# FPGA_System_Monitor.net
KiCad netlist of a schematic drawn in Altium Designer
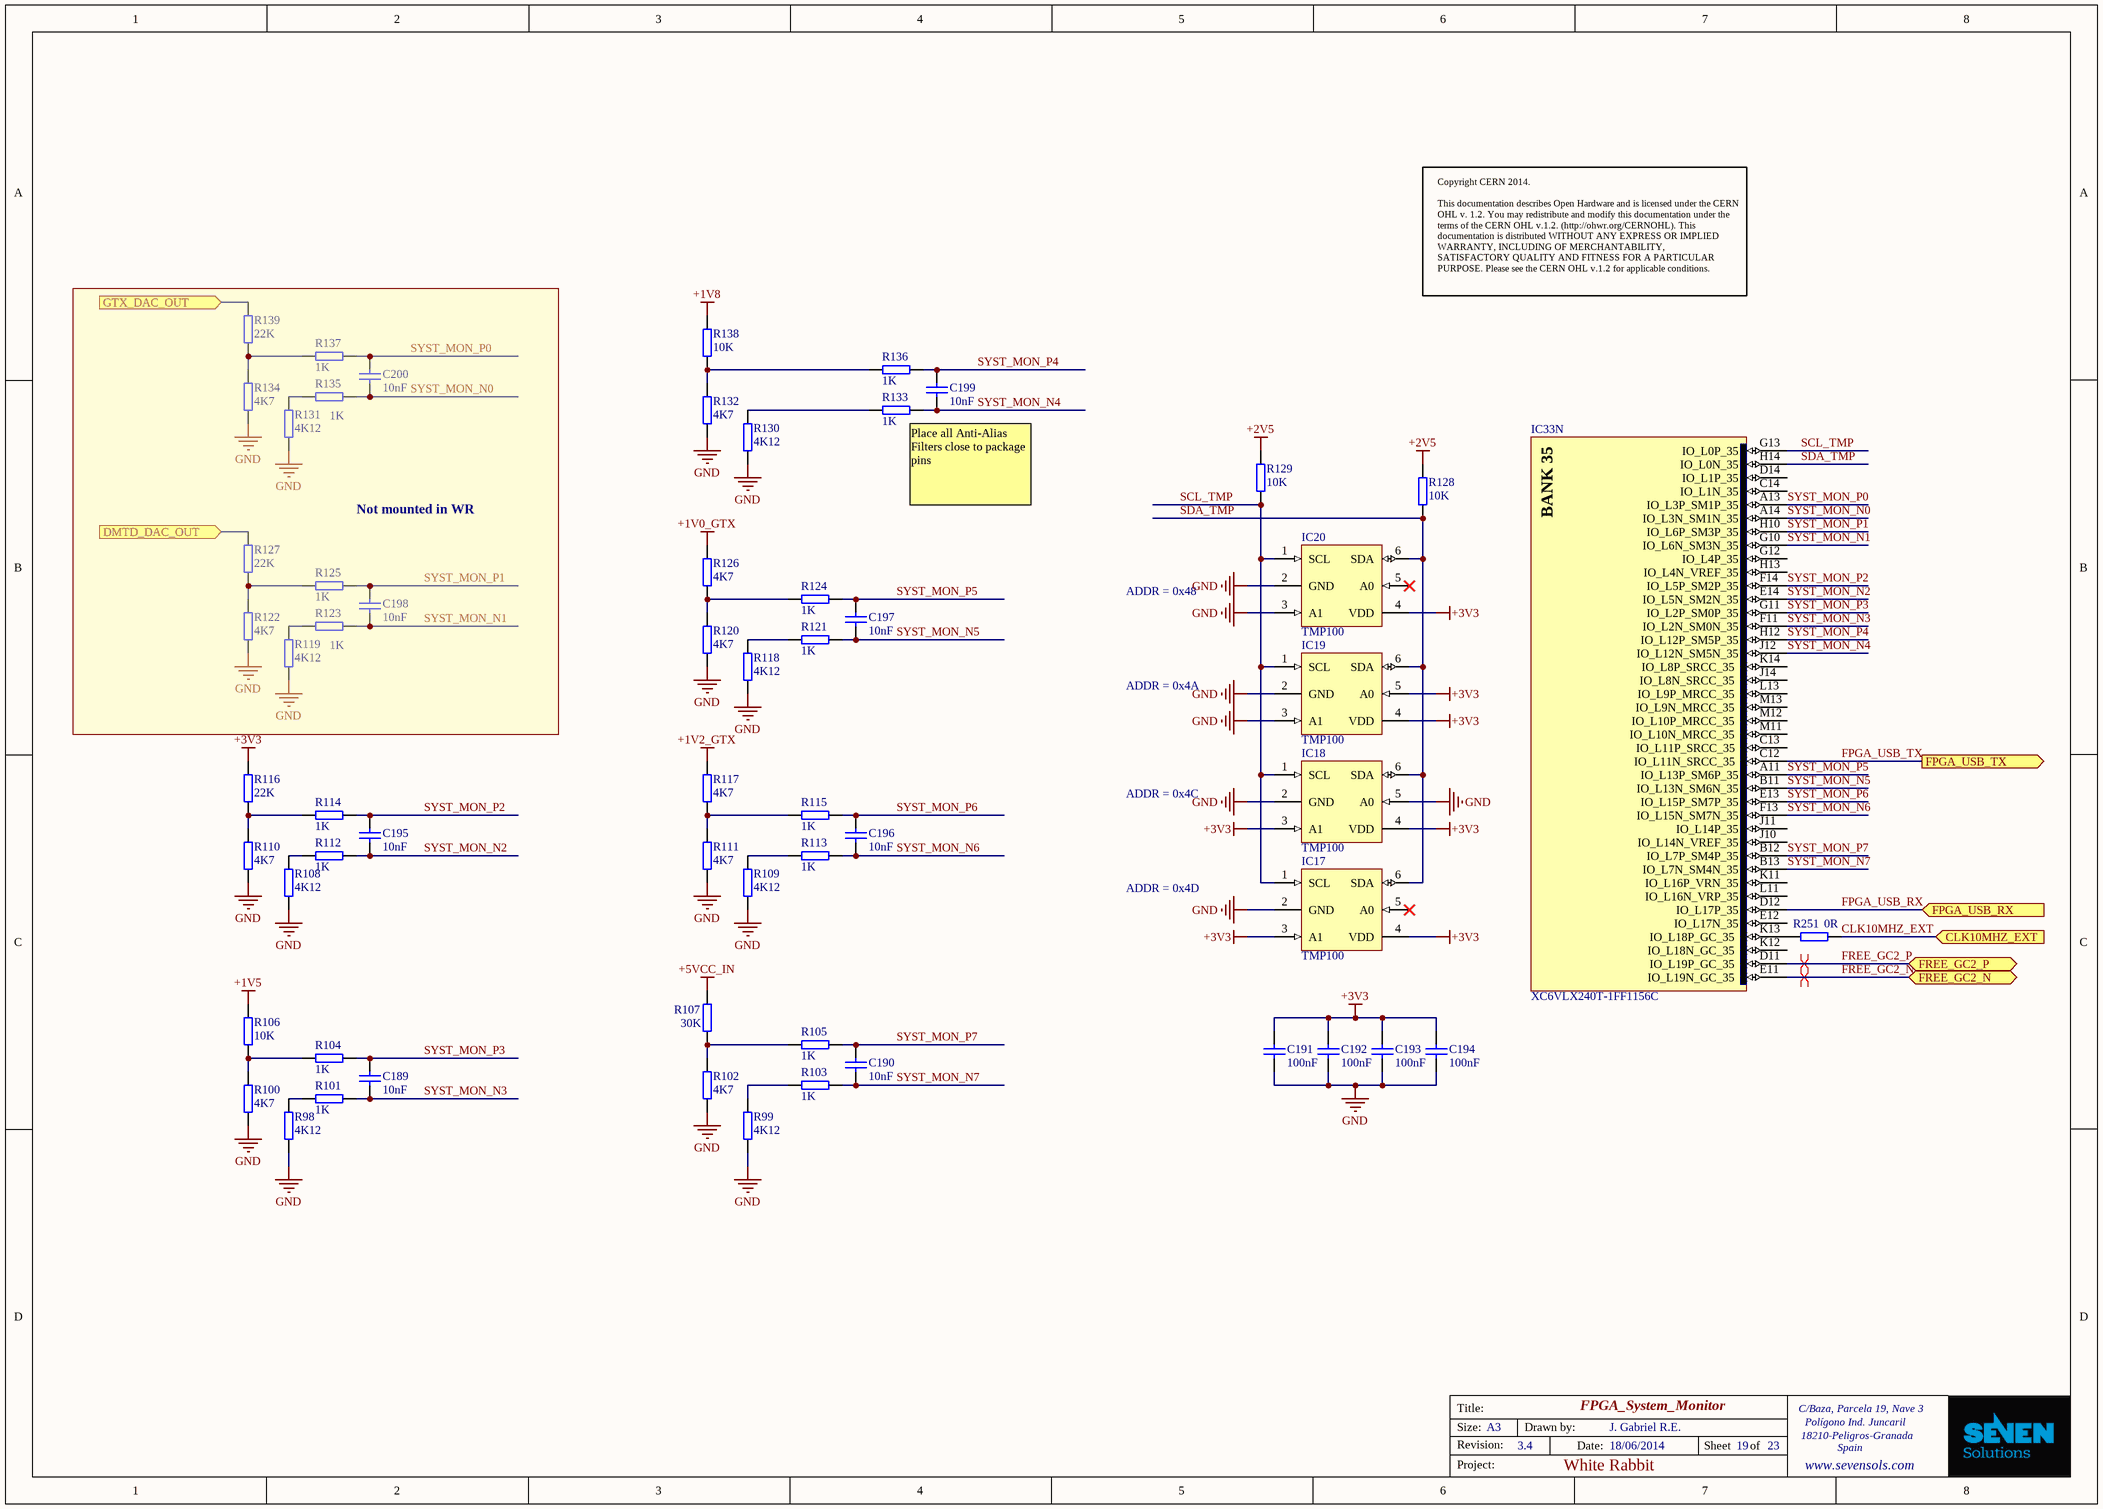
[diagram p0: FPGA_System_Monitor.SchDoc]

(export (version "E")
  (design (tool "Eeschema 10.0.6"))
  (components
    (comp (ref "C189")
      (value "10nF")
      (footprint "CC1005-0402")
      (description "Capacitor")
      (fields
        (field (name "TOLERANCE") "±10%")
        (field (name "VOLTAGE") "25V")
        (field (name "PUBLISHER") "Altium Limited")
      )
      (libsource (lib "wr_switch") (part "Cap"))
    )
    (comp (ref "C190")
      (value "10nF")
      (footprint "CC1005-0402")
      (description "Capacitor")
      (fields
        (field (name "TOLERANCE") "±10%")
        (field (name "VOLTAGE") "25V")
        (field (name "PUBLISHER") "Altium Limited")
      )
      (libsource (lib "wr_switch") (part "Cap"))
    )
    (comp (ref "C191")
      (value "100nF")
      (footprint "CC1005-0402")
      (description "Capacitor")
      (fields
        (field (name "TOLERANCE") "±10%")
        (field (name "VOLTAGE") "16V")
        (field (name "PUBLISHER") "Altium Limited")
      )
      (libsource (lib "wr_switch") (part "Cap"))
    )
    (comp (ref "C192")
      (value "100nF")
      (footprint "CC1005-0402")
      (description "Capacitor")
      (fields
        (field (name "TOLERANCE") "±10%")
        (field (name "VOLTAGE") "16V")
        (field (name "PUBLISHER") "Altium Limited")
      )
      (libsource (lib "wr_switch") (part "Cap"))
    )
    (comp (ref "C193")
      (value "100nF")
      (footprint "CC1005-0402")
      (description "Capacitor")
      (fields
        (field (name "TOLERANCE") "±10%")
        (field (name "VOLTAGE") "16V")
        (field (name "PUBLISHER") "Altium Limited")
      )
      (libsource (lib "wr_switch") (part "Cap"))
    )
    (comp (ref "C194")
      (value "100nF")
      (footprint "CC1005-0402")
      (description "Capacitor")
      (fields
        (field (name "TOLERANCE") "±10%")
        (field (name "VOLTAGE") "16V")
        (field (name "PUBLISHER") "Altium Limited")
      )
      (libsource (lib "wr_switch") (part "Cap"))
    )
    (comp (ref "C195")
      (value "10nF")
      (footprint "CC1005-0402")
      (description "Capacitor")
      (fields
        (field (name "TOLERANCE") "±10%")
        (field (name "VOLTAGE") "25V")
        (field (name "PUBLISHER") "Altium Limited")
      )
      (libsource (lib "wr_switch") (part "Cap"))
    )
    (comp (ref "C196")
      (value "10nF")
      (footprint "CC1005-0402")
      (description "Capacitor")
      (fields
        (field (name "TOLERANCE") "±10%")
        (field (name "VOLTAGE") "25V")
        (field (name "PUBLISHER") "Altium Limited")
      )
      (libsource (lib "wr_switch") (part "Cap"))
    )
    (comp (ref "C197")
      (value "10nF")
      (footprint "CC1005-0402")
      (description "Capacitor")
      (fields
        (field (name "TOLERANCE") "±10%")
        (field (name "VOLTAGE") "25V")
        (field (name "PUBLISHER") "Altium Limited")
      )
      (libsource (lib "wr_switch") (part "Cap"))
    )
    (comp (ref "C198")
      (value "10nF")
      (footprint "CC1005-0402")
      (description "Capacitor")
      (fields
        (field (name "TOLERANCE") "±10%")
        (field (name "VOLTAGE") "25V")
        (field (name "PUBLISHER") "Altium Limited")
      )
      (libsource (lib "wr_switch") (part "Cap"))
    )
    (comp (ref "C199")
      (value "10nF")
      (footprint "CC1005-0402")
      (description "Capacitor")
      (fields
        (field (name "TOLERANCE") "±10%")
        (field (name "VOLTAGE") "25V")
        (field (name "PUBLISHER") "Altium Limited")
      )
      (libsource (lib "wr_switch") (part "Cap"))
    )
    (comp (ref "C200")
      (value "10nF")
      (footprint "CC1005-0402")
      (description "Capacitor")
      (fields
        (field (name "TOLERANCE") "±10%")
        (field (name "VOLTAGE") "25V")
        (field (name "PUBLISHER") "Altium Limited")
      )
      (libsource (lib "wr_switch") (part "Cap"))
    )
    (comp (ref "IC17")
      (value "TMP100")
      (footprint "SOT23A-6L")
      (description "I2C temp. sensor")
      (libsource (lib "wr_switch") (part "TMP100"))
    )
    (comp (ref "IC18")
      (value "TMP100")
      (footprint "SOT23A-6L")
      (description "I2C temp. sensor")
      (libsource (lib "wr_switch") (part "TMP100"))
    )
    (comp (ref "IC19")
      (value "TMP100")
      (footprint "SOT23A-6L")
      (description "I2C temp. sensor")
      (libsource (lib "wr_switch") (part "TMP100"))
    )
    (comp (ref "IC20")
      (value "TMP100")
      (footprint "SOT23A-6L")
      (description "I2C temp. sensor")
      (libsource (lib "wr_switch") (part "TMP100"))
    )
    (comp (ref "IC33")
      (value "XC6VLX240T-1FF1156C")
      (footprint "FF1156")
      (fields (field (name "PUBLISHER") "Altium Limited"))
      (libsource (lib "Xilinx Virtex-6") (part "XC6VLX240T-1FF1156C"))
    )
    (comp (ref "R98")
      (value "4K12")
      (footprint "0402")
      (description "SMD Resistor")
      (fields (field (name "TOLERANCE") "±1%"))
      (libsource (lib "wr_switch") (part "RES_SMD"))
    )
    (comp (ref "R99")
      (value "4K12")
      (footprint "0402")
      (description "SMD Resistor")
      (fields (field (name "TOLERANCE") "±1%"))
      (libsource (lib "wr_switch") (part "RES_SMD"))
    )
    (comp (ref "R100")
      (value "4K7")
      (footprint "0402")
      (description "SMD Resistor")
      (fields (field (name "TOLERANCE") "±1%"))
      (libsource (lib "wr_switch") (part "RES_SMD"))
    )
    (comp (ref "R101")
      (value "1K")
      (footprint "0402")
      (description "SMD Resistor")
      (fields (field (name "TOLERANCE") "±1%"))
      (libsource (lib "wr_switch") (part "RES_SMD"))
    )
    (comp (ref "R102")
      (value "4K7")
      (footprint "0402")
      (description "SMD Resistor")
      (fields (field (name "TOLERANCE") "±1%"))
      (libsource (lib "wr_switch") (part "RES_SMD"))
    )
    (comp (ref "R103")
      (value "1K")
      (footprint "0402")
      (description "SMD Resistor")
      (fields (field (name "TOLERANCE") "±1%"))
      (libsource (lib "wr_switch") (part "RES_SMD"))
    )
    (comp (ref "R104")
      (value "1K")
      (footprint "0402")
      (description "SMD Resistor")
      (fields (field (name "TOLERANCE") "±1%"))
      (libsource (lib "wr_switch") (part "RES_SMD"))
    )
    (comp (ref "R105")
      (value "1K")
      (footprint "0402")
      (description "SMD Resistor")
      (fields (field (name "TOLERANCE") "±1%"))
      (libsource (lib "wr_switch") (part "RES_SMD"))
    )
    (comp (ref "R106")
      (value "10K")
      (footprint "0402")
      (description "SMD Resistor")
      (fields (field (name "TOLERANCE") "±1%") (field (name "Comment") "10k"))
      (libsource (lib "wr_switch") (part "RES_SMD"))
    )
    (comp (ref "R107")
      (value "30K")
      (footprint "0402")
      (description "SMD Resistor")
      (fields (field (name "TOLERANCE") "±1%"))
      (libsource (lib "wr_switch") (part "RES_SMD"))
    )
    (comp (ref "R108")
      (value "4K12")
      (footprint "0402")
      (description "SMD Resistor")
      (fields (field (name "TOLERANCE") "±1%"))
      (libsource (lib "wr_switch") (part "RES_SMD"))
    )
    (comp (ref "R109")
      (value "4K12")
      (footprint "0402")
      (description "SMD Resistor")
      (fields (field (name "TOLERANCE") "±1%"))
      (libsource (lib "wr_switch") (part "RES_SMD"))
    )
    (comp (ref "R110")
      (value "4K7")
      (footprint "0402")
      (description "SMD Resistor")
      (fields (field (name "TOLERANCE") "±1%"))
      (libsource (lib "wr_switch") (part "RES_SMD"))
    )
    (comp (ref "R111")
      (value "4K7")
      (footprint "0402")
      (description "SMD Resistor")
      (fields (field (name "TOLERANCE") "±1%"))
      (libsource (lib "wr_switch") (part "RES_SMD"))
    )
    (comp (ref "R112")
      (value "1K")
      (footprint "0402")
      (description "SMD Resistor")
      (fields (field (name "TOLERANCE") "±1%"))
      (libsource (lib "wr_switch") (part "RES_SMD"))
    )
    (comp (ref "R113")
      (value "1K")
      (footprint "0402")
      (description "SMD Resistor")
      (fields (field (name "TOLERANCE") "±1%"))
      (libsource (lib "wr_switch") (part "RES_SMD"))
    )
    (comp (ref "R114")
      (value "1K")
      (footprint "0402")
      (description "SMD Resistor")
      (fields (field (name "TOLERANCE") "±1%"))
      (libsource (lib "wr_switch") (part "RES_SMD"))
    )
    (comp (ref "R115")
      (value "1K")
      (footprint "0402")
      (description "SMD Resistor")
      (fields (field (name "TOLERANCE") "±1%"))
      (libsource (lib "wr_switch") (part "RES_SMD"))
    )
    (comp (ref "R116")
      (value "22K")
      (footprint "0402")
      (description "SMD Resistor")
      (fields (field (name "TOLERANCE") "±1%"))
      (libsource (lib "wr_switch") (part "RES_SMD"))
    )
    (comp (ref "R117")
      (value "4K7")
      (footprint "0402")
      (description "SMD Resistor")
      (fields (field (name "TOLERANCE") "±1%"))
      (libsource (lib "wr_switch") (part "RES_SMD"))
    )
    (comp (ref "R118")
      (value "4K12")
      (footprint "0402")
      (description "SMD Resistor")
      (fields (field (name "TOLERANCE") "±1%"))
      (libsource (lib "wr_switch") (part "RES_SMD"))
    )
    (comp (ref "R119")
      (value "4K12")
      (footprint "0402")
      (description "SMD Resistor")
      (fields (field (name "TOLERANCE") "±1%"))
      (libsource (lib "wr_switch") (part "RES_SMD"))
    )
    (comp (ref "R120")
      (value "4K7")
      (footprint "0402")
      (description "SMD Resistor")
      (fields (field (name "TOLERANCE") "±1%"))
      (libsource (lib "wr_switch") (part "RES_SMD"))
    )
    (comp (ref "R121")
      (value "1K")
      (footprint "0402")
      (description "SMD Resistor")
      (fields (field (name "TOLERANCE") "±1%"))
      (libsource (lib "wr_switch") (part "RES_SMD"))
    )
    (comp (ref "R122")
      (value "4K7")
      (footprint "0402")
      (description "SMD Resistor")
      (fields (field (name "TOLERANCE") "±1%"))
      (libsource (lib "wr_switch") (part "RES_SMD"))
    )
    (comp (ref "R123")
      (value "1K")
      (footprint "0402")
      (description "SMD Resistor")
      (fields (field (name "TOLERANCE") "±1%"))
      (libsource (lib "wr_switch") (part "RES_SMD"))
    )
    (comp (ref "R124")
      (value "1K")
      (footprint "0402")
      (description "SMD Resistor")
      (fields (field (name "TOLERANCE") "±1%"))
      (libsource (lib "wr_switch") (part "RES_SMD"))
    )
    (comp (ref "R125")
      (value "1K")
      (footprint "0402")
      (description "SMD Resistor")
      (fields (field (name "TOLERANCE") "±1%"))
      (libsource (lib "wr_switch") (part "RES_SMD"))
    )
    (comp (ref "R126")
      (value "4K7")
      (footprint "0402")
      (description "SMD Resistor")
      (fields (field (name "TOLERANCE") "±1%"))
      (libsource (lib "wr_switch") (part "RES_SMD"))
    )
    (comp (ref "R127")
      (value "22K")
      (footprint "0402")
      (description "SMD Resistor")
      (fields (field (name "TOLERANCE") "±1%"))
      (libsource (lib "wr_switch") (part "RES_SMD"))
    )
    (comp (ref "R128")
      (value "10K")
      (footprint "0402")
      (description "SMD Resistor")
      (fields (field (name "TOLERANCE") "±1%") (field (name "Comment") "10k"))
      (libsource (lib "wr_switch") (part "RES_SMD"))
    )
    (comp (ref "R129")
      (value "10K")
      (footprint "0402")
      (description "SMD Resistor")
      (fields (field (name "TOLERANCE") "±1%") (field (name "Comment") "10k"))
      (libsource (lib "wr_switch") (part "RES_SMD"))
    )
    (comp (ref "R130")
      (value "4K12")
      (footprint "0402")
      (description "SMD Resistor")
      (fields (field (name "TOLERANCE") "±1%"))
      (libsource (lib "wr_switch") (part "RES_SMD"))
    )
    (comp (ref "R131")
      (value "4K12")
      (footprint "0402")
      (description "SMD Resistor")
      (fields (field (name "TOLERANCE") "±1%"))
      (libsource (lib "wr_switch") (part "RES_SMD"))
    )
    (comp (ref "R132")
      (value "4K7")
      (footprint "0402")
      (description "SMD Resistor")
      (fields (field (name "TOLERANCE") "±1%"))
      (libsource (lib "wr_switch") (part "RES_SMD"))
    )
    (comp (ref "R133")
      (value "1K")
      (footprint "0402")
      (description "SMD Resistor")
      (fields (field (name "TOLERANCE") "±1%"))
      (libsource (lib "wr_switch") (part "RES_SMD"))
    )
    (comp (ref "R134")
      (value "4K7")
      (footprint "0402")
      (description "SMD Resistor")
      (fields (field (name "TOLERANCE") "±1%"))
      (libsource (lib "wr_switch") (part "RES_SMD"))
    )
    (comp (ref "R135")
      (value "1K")
      (footprint "0402")
      (description "SMD Resistor")
      (fields (field (name "TOLERANCE") "±1%"))
      (libsource (lib "wr_switch") (part "RES_SMD"))
    )
    (comp (ref "R136")
      (value "1K")
      (footprint "0402")
      (description "SMD Resistor")
      (fields (field (name "TOLERANCE") "±1%"))
      (libsource (lib "wr_switch") (part "RES_SMD"))
    )
    (comp (ref "R137")
      (value "1K")
      (footprint "0402")
      (description "SMD Resistor")
      (fields (field (name "TOLERANCE") "±1%"))
      (libsource (lib "wr_switch") (part "RES_SMD"))
    )
    (comp (ref "R138")
      (value "10K")
      (footprint "0402")
      (description "SMD Resistor")
      (fields (field (name "TOLERANCE") "±1%") (field (name "Comment") "10k"))
      (libsource (lib "wr_switch") (part "RES_SMD"))
    )
    (comp (ref "R139")
      (value "22K")
      (footprint "0402")
      (description "SMD Resistor")
      (fields (field (name "TOLERANCE") "±1%"))
      (libsource (lib "wr_switch") (part "RES_SMD"))
    )
    (comp (ref "R251")
      (value "0R")
      (footprint "0402")
      (description "SMD Resistor")
      (fields (field (name "TOLERANCE") "Jumper"))
      (libsource (lib "wr_switch") (part "RES_SMD"))
    )
  )
  (nets
    (net (code "1") (name "+1V0_GTX") (class "Default")
      (node (ref "R126") (pin "2") (pinfunction "2_2") (pintype "passive"))
    )
    (net (code "2") (name "+1V2_GTX") (class "Default")
      (node (ref "R117") (pin "2") (pinfunction "2_2") (pintype "passive"))
    )
    (net (code "3") (name "+1V5") (class "Default")
      (node (ref "R106") (pin "2") (pinfunction "2_2") (pintype "passive"))
    )
    (net (code "4") (name "+1V8") (class "Default")
      (node (ref "R138") (pin "2") (pinfunction "2_2") (pintype "passive"))
    )
    (net (code "5") (name "+2V5") (class "Default")
      (node (ref "R128") (pin "2") (pinfunction "2_2") (pintype "passive"))
      (node (ref "R129") (pin "2") (pinfunction "2_2") (pintype "passive"))
    )
    (net (code "6") (name "+3V3") (class "Default")
      (node (ref "C191") (pin "1") (pinfunction "1_1") (pintype "passive"))
      (node (ref "C192") (pin "1") (pinfunction "1_1") (pintype "passive"))
      (node (ref "C193") (pin "1") (pinfunction "1_1") (pintype "passive"))
      (node (ref "C194") (pin "1") (pinfunction "1_1") (pintype "passive"))
      (node (ref "IC17") (pin "3") (pinfunction "A1_3") (pintype "input"))
      (node (ref "IC17") (pin "4") (pinfunction "VDD_4") (pintype "power_in"))
      (node (ref "IC18") (pin "3") (pinfunction "A1_3") (pintype "input"))
      (node (ref "IC18") (pin "4") (pinfunction "VDD_4") (pintype "power_in"))
      (node (ref "IC19") (pin "4") (pinfunction "VDD_4") (pintype "power_in"))
      (node (ref "IC19") (pin "5") (pinfunction "A0_5") (pintype "input"))
      (node (ref "IC20") (pin "4") (pinfunction "VDD_4") (pintype "power_in"))
      (node (ref "R116") (pin "2") (pinfunction "2_2") (pintype "passive"))
    )
    (net (code "7") (name "+5VCC_IN") (class "Default")
      (node (ref "R107") (pin "2") (pinfunction "2_2") (pintype "passive"))
    )
    (net (code "8") (name "/CLK10MHZ_EXT") (class "Default")
      (node (ref "R251") (pin "1") (pinfunction "1_1") (pintype "passive"))
    )
    (net (code "9") (name "/DMTD_DAC_OUT") (class "Default")
      (node (ref "R127") (pin "2") (pinfunction "2_2") (pintype "passive"))
    )
    (net (code "10") (name "/FPGA_USB_RX") (class "Default")
      (node (ref "IC33") (pin "D12") (pinfunction "IO_L17P_35_D12") (pintype "bidirectional"))
    )
    (net (code "11") (name "/FPGA_USB_TX") (class "Default")
      (node (ref "IC33") (pin "C12") (pinfunction "IO_L11N_SRCC_35_C12") (pintype "bidirectional"))
    )
    (net (code "12") (name "/FREE_GC2_N") (class "Default")
      (node (ref "IC33") (pin "E11") (pinfunction "IO_L19N_GC_35_E11") (pintype "bidirectional"))
    )
    (net (code "13") (name "/FREE_GC2_P") (class "Default")
      (node (ref "IC33") (pin "D11") (pinfunction "IO_L19P_GC_35_D11") (pintype "bidirectional"))
    )
    (net (code "14") (name "/GTX_DAC_OUT") (class "Default")
      (node (ref "R139") (pin "2") (pinfunction "2_2") (pintype "passive"))
    )
    (net (code "15") (name "/SCL_TMP") (class "Default")
      (node (ref "IC17") (pin "1") (pinfunction "SCL_1") (pintype "input"))
      (node (ref "IC18") (pin "1") (pinfunction "SCL_1") (pintype "input"))
      (node (ref "IC19") (pin "1") (pinfunction "SCL_1") (pintype "input"))
      (node (ref "IC20") (pin "1") (pinfunction "SCL_1") (pintype "input"))
      (node (ref "IC33") (pin "G13") (pinfunction "IO_L0P_35_G13") (pintype "bidirectional"))
      (node (ref "R129") (pin "1") (pinfunction "1_1") (pintype "passive"))
    )
    (net (code "16") (name "/SDA_TMP") (class "Default")
      (node (ref "IC17") (pin "6") (pinfunction "SDA_6") (pintype "bidirectional"))
      (node (ref "IC18") (pin "6") (pinfunction "SDA_6") (pintype "bidirectional"))
      (node (ref "IC19") (pin "6") (pinfunction "SDA_6") (pintype "bidirectional"))
      (node (ref "IC20") (pin "6") (pinfunction "SDA_6") (pintype "bidirectional"))
      (node (ref "IC33") (pin "H14") (pinfunction "IO_L0N_35_H14") (pintype "bidirectional"))
      (node (ref "R128") (pin "1") (pinfunction "1_1") (pintype "passive"))
    )
    (net (code "17") (name "/SYST_MON_N0") (class "Default")
      (node (ref "C200") (pin "1") (pinfunction "1_1") (pintype "passive"))
      (node (ref "IC33") (pin "A14") (pinfunction "IO_L3N_SM1N_35_A14") (pintype "bidirectional"))
      (node (ref "R135") (pin "1") (pinfunction "1_1") (pintype "passive"))
    )
    (net (code "18") (name "/SYST_MON_N1") (class "Default")
      (node (ref "C198") (pin "1") (pinfunction "1_1") (pintype "passive"))
      (node (ref "IC33") (pin "G10") (pinfunction "IO_L6N_SM3N_35_G10") (pintype "bidirectional"))
      (node (ref "R123") (pin "1") (pinfunction "1_1") (pintype "passive"))
    )
    (net (code "19") (name "/SYST_MON_N2") (class "Default")
      (node (ref "C195") (pin "1") (pinfunction "1_1") (pintype "passive"))
      (node (ref "IC33") (pin "E14") (pinfunction "IO_L5N_SM2N_35_E14") (pintype "bidirectional"))
      (node (ref "R112") (pin "1") (pinfunction "1_1") (pintype "passive"))
    )
    (net (code "20") (name "/SYST_MON_N3") (class "Default")
      (node (ref "C189") (pin "1") (pinfunction "1_1") (pintype "passive"))
      (node (ref "IC33") (pin "F11") (pinfunction "IO_L2N_SM0N_35_F11") (pintype "bidirectional"))
      (node (ref "R101") (pin "1") (pinfunction "1_1") (pintype "passive"))
    )
    (net (code "21") (name "/SYST_MON_N4") (class "Default")
      (node (ref "C199") (pin "1") (pinfunction "1_1") (pintype "passive"))
      (node (ref "IC33") (pin "J12") (pinfunction "IO_L12N_SM5N_35_J12") (pintype "bidirectional"))
      (node (ref "R133") (pin "1") (pinfunction "1_1") (pintype "passive"))
    )
    (net (code "22") (name "/SYST_MON_N5") (class "Default")
      (node (ref "C197") (pin "1") (pinfunction "1_1") (pintype "passive"))
      (node (ref "IC33") (pin "B11") (pinfunction "IO_L13N_SM6N_35_B11") (pintype "bidirectional"))
      (node (ref "R121") (pin "1") (pinfunction "1_1") (pintype "passive"))
    )
    (net (code "23") (name "/SYST_MON_N6") (class "Default")
      (node (ref "C196") (pin "1") (pinfunction "1_1") (pintype "passive"))
      (node (ref "IC33") (pin "F13") (pinfunction "IO_L15N_SM7N_35_F13") (pintype "bidirectional"))
      (node (ref "R113") (pin "1") (pinfunction "1_1") (pintype "passive"))
    )
    (net (code "24") (name "/SYST_MON_N7") (class "Default")
      (node (ref "C190") (pin "1") (pinfunction "1_1") (pintype "passive"))
      (node (ref "IC33") (pin "B13") (pinfunction "IO_L7N_SM4N_35_B13") (pintype "bidirectional"))
      (node (ref "R103") (pin "1") (pinfunction "1_1") (pintype "passive"))
    )
    (net (code "25") (name "/SYST_MON_P0") (class "Default")
      (node (ref "C200") (pin "2") (pinfunction "2_2") (pintype "passive"))
      (node (ref "IC33") (pin "A13") (pinfunction "IO_L3P_SM1P_35_A13") (pintype "bidirectional"))
      (node (ref "R137") (pin "1") (pinfunction "1_1") (pintype "passive"))
    )
    (net (code "26") (name "/SYST_MON_P1") (class "Default")
      (node (ref "C198") (pin "2") (pinfunction "2_2") (pintype "passive"))
      (node (ref "IC33") (pin "H10") (pinfunction "IO_L6P_SM3P_35_H10") (pintype "bidirectional"))
      (node (ref "R125") (pin "1") (pinfunction "1_1") (pintype "passive"))
    )
    (net (code "27") (name "/SYST_MON_P2") (class "Default")
      (node (ref "C195") (pin "2") (pinfunction "2_2") (pintype "passive"))
      (node (ref "IC33") (pin "F14") (pinfunction "IO_L5P_SM2P_35_F14") (pintype "bidirectional"))
      (node (ref "R114") (pin "1") (pinfunction "1_1") (pintype "passive"))
    )
    (net (code "28") (name "/SYST_MON_P3") (class "Default")
      (node (ref "C189") (pin "2") (pinfunction "2_2") (pintype "passive"))
      (node (ref "IC33") (pin "G11") (pinfunction "IO_L2P_SM0P_35_G11") (pintype "bidirectional"))
      (node (ref "R104") (pin "1") (pinfunction "1_1") (pintype "passive"))
    )
    (net (code "29") (name "/SYST_MON_P4") (class "Default")
      (node (ref "C199") (pin "2") (pinfunction "2_2") (pintype "passive"))
      (node (ref "IC33") (pin "H12") (pinfunction "IO_L12P_SM5P_35_H12") (pintype "bidirectional"))
      (node (ref "R136") (pin "1") (pinfunction "1_1") (pintype "passive"))
    )
    (net (code "30") (name "/SYST_MON_P5") (class "Default")
      (node (ref "C197") (pin "2") (pinfunction "2_2") (pintype "passive"))
      (node (ref "IC33") (pin "A11") (pinfunction "IO_L13P_SM6P_35_A11") (pintype "bidirectional"))
      (node (ref "R124") (pin "1") (pinfunction "1_1") (pintype "passive"))
    )
    (net (code "31") (name "/SYST_MON_P6") (class "Default")
      (node (ref "C196") (pin "2") (pinfunction "2_2") (pintype "passive"))
      (node (ref "IC33") (pin "E13") (pinfunction "IO_L15P_SM7P_35_E13") (pintype "bidirectional"))
      (node (ref "R115") (pin "1") (pinfunction "1_1") (pintype "passive"))
    )
    (net (code "32") (name "/SYST_MON_P7") (class "Default")
      (node (ref "C190") (pin "2") (pinfunction "2_2") (pintype "passive"))
      (node (ref "IC33") (pin "B12") (pinfunction "IO_L7P_SM4P_35_B12") (pintype "bidirectional"))
      (node (ref "R105") (pin "1") (pinfunction "1_1") (pintype "passive"))
    )
    (net (code "33") (name "GND") (class "Default")
      (node (ref "C191") (pin "2") (pinfunction "2_2") (pintype "passive"))
      (node (ref "C192") (pin "2") (pinfunction "2_2") (pintype "passive"))
      (node (ref "C193") (pin "2") (pinfunction "2_2") (pintype "passive"))
      (node (ref "C194") (pin "2") (pinfunction "2_2") (pintype "passive"))
      (node (ref "IC17") (pin "2") (pinfunction "GND_2") (pintype "power_in"))
      (node (ref "IC18") (pin "2") (pinfunction "GND_2") (pintype "power_in"))
      (node (ref "IC18") (pin "5") (pinfunction "A0_5") (pintype "input"))
      (node (ref "IC19") (pin "2") (pinfunction "GND_2") (pintype "power_in"))
      (node (ref "IC19") (pin "3") (pinfunction "A1_3") (pintype "input"))
      (node (ref "IC20") (pin "2") (pinfunction "GND_2") (pintype "power_in"))
      (node (ref "IC20") (pin "3") (pinfunction "A1_3") (pintype "input"))
      (node (ref "R100") (pin "1") (pinfunction "1_1") (pintype "passive"))
      (node (ref "R102") (pin "1") (pinfunction "1_1") (pintype "passive"))
      (node (ref "R108") (pin "1") (pinfunction "1_1") (pintype "passive"))
      (node (ref "R109") (pin "1") (pinfunction "1_1") (pintype "passive"))
      (node (ref "R110") (pin "1") (pinfunction "1_1") (pintype "passive"))
      (node (ref "R111") (pin "1") (pinfunction "1_1") (pintype "passive"))
      (node (ref "R118") (pin "1") (pinfunction "1_1") (pintype "passive"))
      (node (ref "R119") (pin "1") (pinfunction "1_1") (pintype "passive"))
      (node (ref "R120") (pin "1") (pinfunction "1_1") (pintype "passive"))
      (node (ref "R122") (pin "1") (pinfunction "1_1") (pintype "passive"))
      (node (ref "R130") (pin "1") (pinfunction "1_1") (pintype "passive"))
      (node (ref "R131") (pin "1") (pinfunction "1_1") (pintype "passive"))
      (node (ref "R132") (pin "1") (pinfunction "1_1") (pintype "passive"))
      (node (ref "R134") (pin "1") (pinfunction "1_1") (pintype "passive"))
      (node (ref "R98") (pin "1") (pinfunction "1_1") (pintype "passive"))
      (node (ref "R99") (pin "1") (pinfunction "1_1") (pintype "passive"))
    )
    (net (code "34") (name "Net-(IC33N-IO_L18P_GC_35)") (class "Default")
      (node (ref "IC33") (pin "K13") (pinfunction "IO_L18P_GC_35_K13") (pintype "bidirectional"))
      (node (ref "R251") (pin "2") (pinfunction "2_2") (pintype "passive"))
    )
    (net (code "35") (name "Net-(R100-Pad2)") (class "Default")
      (node (ref "R100") (pin "2") (pinfunction "2_2") (pintype "passive"))
      (node (ref "R104") (pin "2") (pinfunction "2_2") (pintype "passive"))
      (node (ref "R106") (pin "1") (pinfunction "1_1") (pintype "passive"))
    )
    (net (code "36") (name "Net-(R101-Pad2)") (class "Default")
      (node (ref "R101") (pin "2") (pinfunction "2_2") (pintype "passive"))
      (node (ref "R98") (pin "2") (pinfunction "2_2") (pintype "passive"))
    )
    (net (code "37") (name "Net-(R102-Pad2)") (class "Default")
      (node (ref "R102") (pin "2") (pinfunction "2_2") (pintype "passive"))
      (node (ref "R105") (pin "2") (pinfunction "2_2") (pintype "passive"))
      (node (ref "R107") (pin "1") (pinfunction "1_1") (pintype "passive"))
    )
    (net (code "38") (name "Net-(R103-Pad2)") (class "Default")
      (node (ref "R103") (pin "2") (pinfunction "2_2") (pintype "passive"))
      (node (ref "R99") (pin "2") (pinfunction "2_2") (pintype "passive"))
    )
    (net (code "39") (name "Net-(R108-Pad2)") (class "Default")
      (node (ref "R108") (pin "2") (pinfunction "2_2") (pintype "passive"))
      (node (ref "R112") (pin "2") (pinfunction "2_2") (pintype "passive"))
    )
    (net (code "40") (name "Net-(R109-Pad2)") (class "Default")
      (node (ref "R109") (pin "2") (pinfunction "2_2") (pintype "passive"))
      (node (ref "R113") (pin "2") (pinfunction "2_2") (pintype "passive"))
    )
    (net (code "41") (name "Net-(R110-Pad2)") (class "Default")
      (node (ref "R110") (pin "2") (pinfunction "2_2") (pintype "passive"))
      (node (ref "R114") (pin "2") (pinfunction "2_2") (pintype "passive"))
      (node (ref "R116") (pin "1") (pinfunction "1_1") (pintype "passive"))
    )
    (net (code "42") (name "Net-(R111-Pad2)") (class "Default")
      (node (ref "R111") (pin "2") (pinfunction "2_2") (pintype "passive"))
      (node (ref "R115") (pin "2") (pinfunction "2_2") (pintype "passive"))
      (node (ref "R117") (pin "1") (pinfunction "1_1") (pintype "passive"))
    )
    (net (code "43") (name "Net-(R118-Pad2)") (class "Default")
      (node (ref "R118") (pin "2") (pinfunction "2_2") (pintype "passive"))
      (node (ref "R121") (pin "2") (pinfunction "2_2") (pintype "passive"))
    )
    (net (code "44") (name "Net-(R119-Pad2)") (class "Default")
      (node (ref "R119") (pin "2") (pinfunction "2_2") (pintype "passive"))
      (node (ref "R123") (pin "2") (pinfunction "2_2") (pintype "passive"))
    )
    (net (code "45") (name "Net-(R120-Pad2)") (class "Default")
      (node (ref "R120") (pin "2") (pinfunction "2_2") (pintype "passive"))
      (node (ref "R124") (pin "2") (pinfunction "2_2") (pintype "passive"))
      (node (ref "R126") (pin "1") (pinfunction "1_1") (pintype "passive"))
    )
    (net (code "46") (name "Net-(R122-Pad2)") (class "Default")
      (node (ref "R122") (pin "2") (pinfunction "2_2") (pintype "passive"))
      (node (ref "R125") (pin "2") (pinfunction "2_2") (pintype "passive"))
      (node (ref "R127") (pin "1") (pinfunction "1_1") (pintype "passive"))
    )
    (net (code "47") (name "Net-(R130-Pad2)") (class "Default")
      (node (ref "R130") (pin "2") (pinfunction "2_2") (pintype "passive"))
      (node (ref "R133") (pin "2") (pinfunction "2_2") (pintype "passive"))
    )
    (net (code "48") (name "Net-(R131-Pad2)") (class "Default")
      (node (ref "R131") (pin "2") (pinfunction "2_2") (pintype "passive"))
      (node (ref "R135") (pin "2") (pinfunction "2_2") (pintype "passive"))
    )
    (net (code "49") (name "Net-(R132-Pad2)") (class "Default")
      (node (ref "R132") (pin "2") (pinfunction "2_2") (pintype "passive"))
      (node (ref "R136") (pin "2") (pinfunction "2_2") (pintype "passive"))
      (node (ref "R138") (pin "1") (pinfunction "1_1") (pintype "passive"))
    )
    (net (code "50") (name "Net-(R134-Pad2)") (class "Default")
      (node (ref "R134") (pin "2") (pinfunction "2_2") (pintype "passive"))
      (node (ref "R137") (pin "2") (pinfunction "2_2") (pintype "passive"))
      (node (ref "R139") (pin "1") (pinfunction "1_1") (pintype "passive"))
    )
    (net (code "51") (name "unconnected-(IC17-A0-Pad5)") (class "Default")
      (node (ref "IC17") (pin "5") (pinfunction "A0_5") (pintype "input+no_connect"))
    )
    (net (code "52") (name "unconnected-(IC20-A0-Pad5)") (class "Default")
      (node (ref "IC20") (pin "5") (pinfunction "A0_5") (pintype "input+no_connect"))
    )
    (net (code "53") (name "unconnected-(IC33N-IO_L1N_35-PadC14)") (class "Default")
      (node (ref "IC33") (pin "C14") (pinfunction "IO_L1N_35_C14") (pintype "bidirectional"))
    )
    (net (code "54") (name "unconnected-(IC33N-IO_L1P_35-PadD14)") (class "Default")
      (node (ref "IC33") (pin "D14") (pinfunction "IO_L1P_35_D14") (pintype "bidirectional"))
    )
    (net (code "55") (name "unconnected-(IC33N-IO_L4N_VREF_35-PadH13)") (class "Default")
      (node (ref "IC33") (pin "H13") (pinfunction "IO_L4N_VREF_35_H13") (pintype "bidirectional"))
    )
    (net (code "56") (name "unconnected-(IC33N-IO_L4P_35-PadG12)") (class "Default")
      (node (ref "IC33") (pin "G12") (pinfunction "IO_L4P_35_G12") (pintype "bidirectional"))
    )
    (net (code "57") (name "unconnected-(IC33N-IO_L8N_SRCC_35-PadJ14)") (class "Default")
      (node (ref "IC33") (pin "J14") (pinfunction "IO_L8N_SRCC_35_J14") (pintype "bidirectional"))
    )
    (net (code "58") (name "unconnected-(IC33N-IO_L8P_SRCC_35-PadK14)") (class "Default")
      (node (ref "IC33") (pin "K14") (pinfunction "IO_L8P_SRCC_35_K14") (pintype "bidirectional"))
    )
    (net (code "59") (name "unconnected-(IC33N-IO_L9N_MRCC_35-PadM13)") (class "Default")
      (node (ref "IC33") (pin "M13") (pinfunction "IO_L9N_MRCC_35_M13") (pintype "bidirectional"))
    )
    (net (code "60") (name "unconnected-(IC33N-IO_L9P_MRCC_35-PadL13)") (class "Default")
      (node (ref "IC33") (pin "L13") (pinfunction "IO_L9P_MRCC_35_L13") (pintype "bidirectional"))
    )
    (net (code "61") (name "unconnected-(IC33N-IO_L10N_MRCC_35-PadM11)") (class "Default")
      (node (ref "IC33") (pin "M11") (pinfunction "IO_L10N_MRCC_35_M11") (pintype "bidirectional"))
    )
    (net (code "62") (name "unconnected-(IC33N-IO_L10P_MRCC_35-PadM12)") (class "Default")
      (node (ref "IC33") (pin "M12") (pinfunction "IO_L10P_MRCC_35_M12") (pintype "bidirectional"))
    )
    (net (code "63") (name "unconnected-(IC33N-IO_L11P_SRCC_35-PadC13)") (class "Default")
      (node (ref "IC33") (pin "C13") (pinfunction "IO_L11P_SRCC_35_C13") (pintype "bidirectional"))
    )
    (net (code "64") (name "unconnected-(IC33N-IO_L14N_VREF_35-PadJ10)") (class "Default")
      (node (ref "IC33") (pin "J10") (pinfunction "IO_L14N_VREF_35_J10") (pintype "bidirectional"))
    )
    (net (code "65") (name "unconnected-(IC33N-IO_L14P_35-PadJ11)") (class "Default")
      (node (ref "IC33") (pin "J11") (pinfunction "IO_L14P_35_J11") (pintype "bidirectional"))
    )
    (net (code "66") (name "unconnected-(IC33N-IO_L16N_VRP_35-PadL11)") (class "Default")
      (node (ref "IC33") (pin "L11") (pinfunction "IO_L16N_VRP_35_L11") (pintype "bidirectional"))
    )
    (net (code "67") (name "unconnected-(IC33N-IO_L16P_VRN_35-PadK11)") (class "Default")
      (node (ref "IC33") (pin "K11") (pinfunction "IO_L16P_VRN_35_K11") (pintype "bidirectional"))
    )
    (net (code "68") (name "unconnected-(IC33N-IO_L17N_35-PadE12)") (class "Default")
      (node (ref "IC33") (pin "E12") (pinfunction "IO_L17N_35_E12") (pintype "bidirectional"))
    )
    (net (code "69") (name "unconnected-(IC33N-IO_L18N_GC_35-PadK12)") (class "Default")
      (node (ref "IC33") (pin "K12") (pinfunction "IO_L18N_GC_35_K12") (pintype "bidirectional"))
    )
  )
)
